# schematic.net
KiCad netlist of a schematic drawn in EAGLE
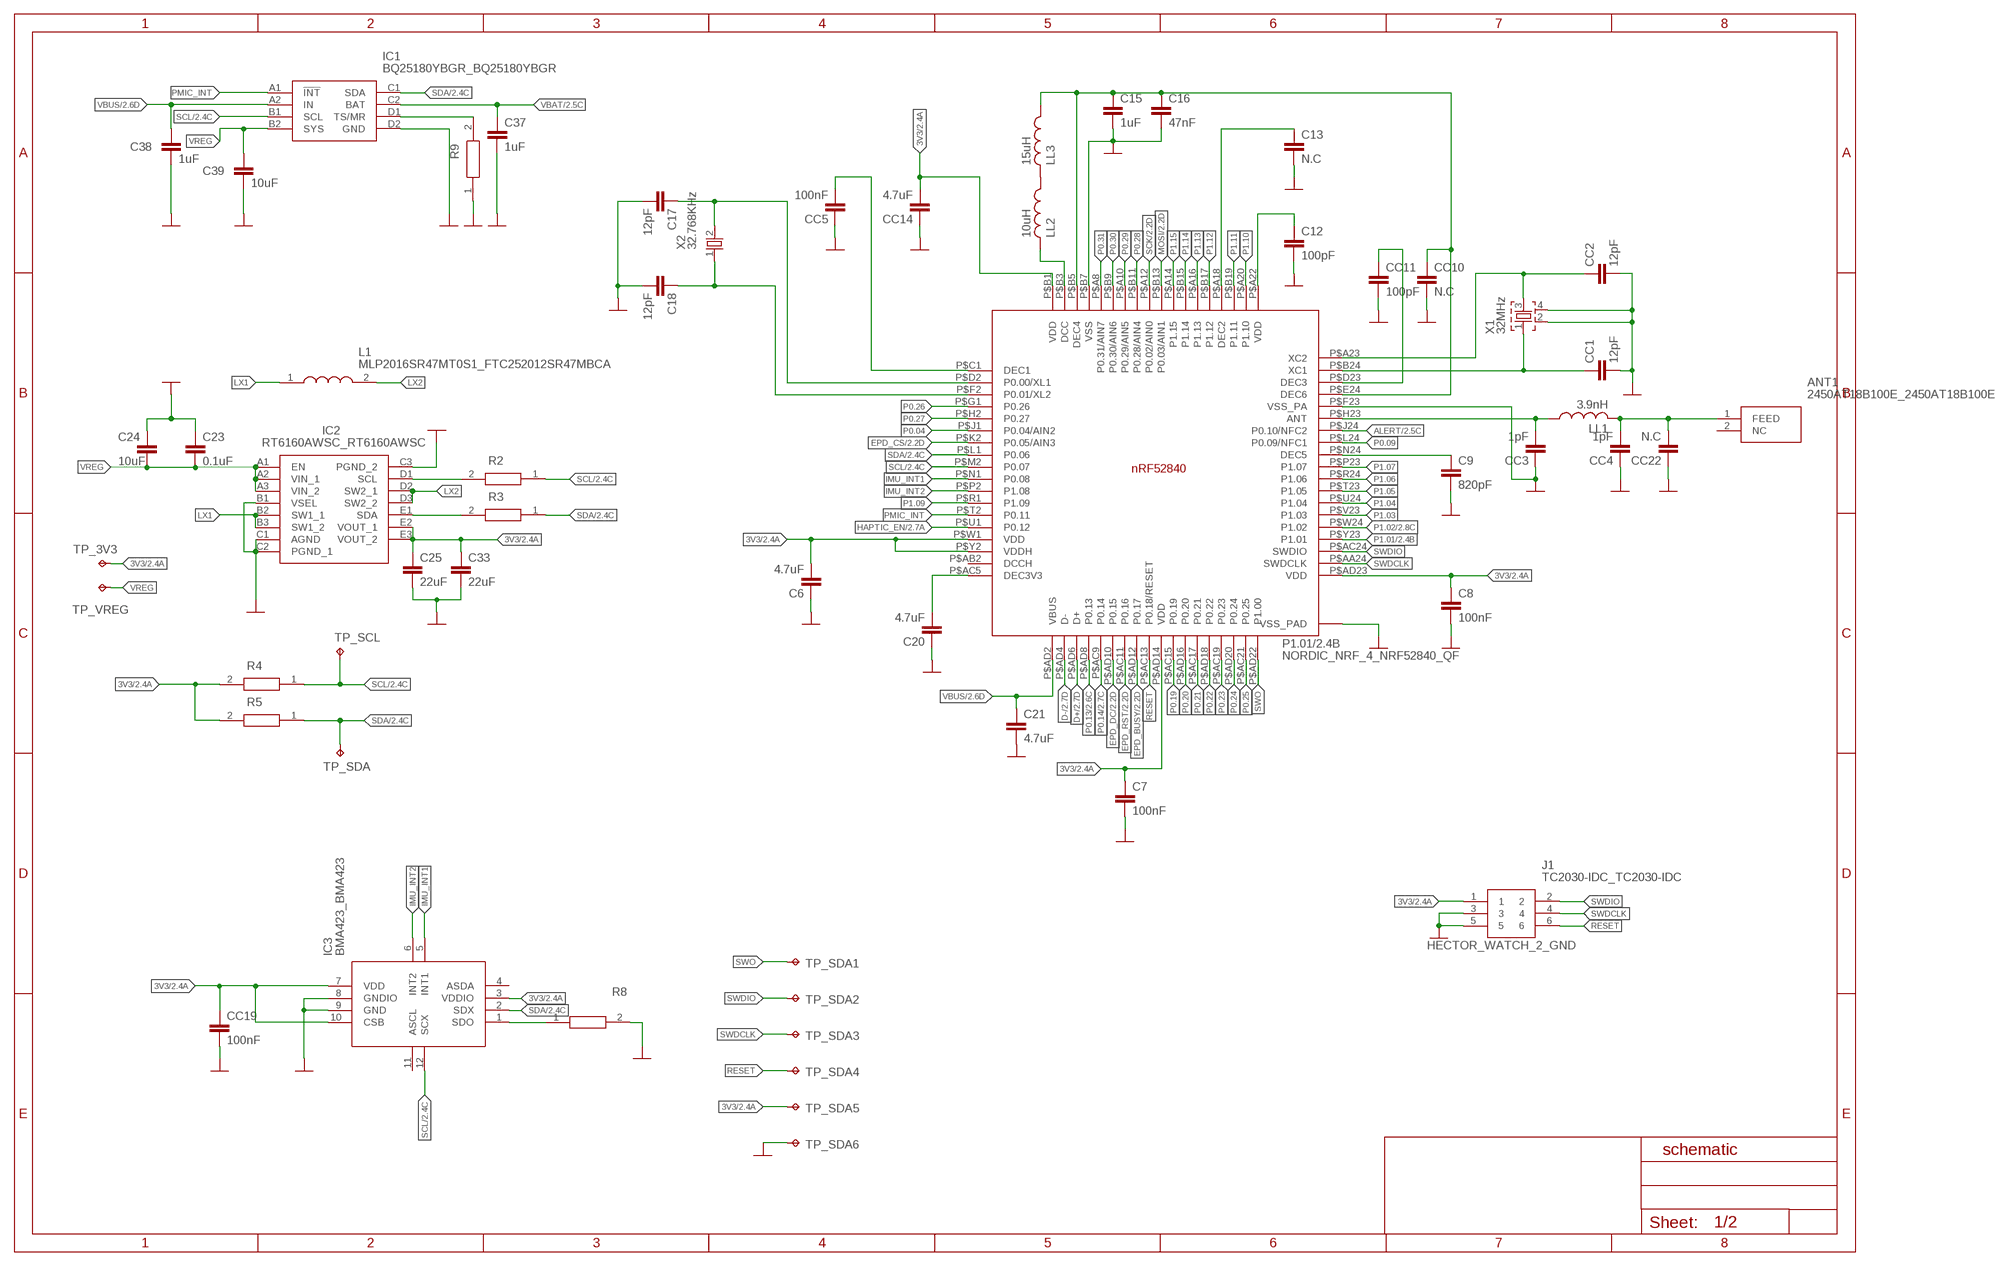
[diagram p0: schematic, sheet 1]
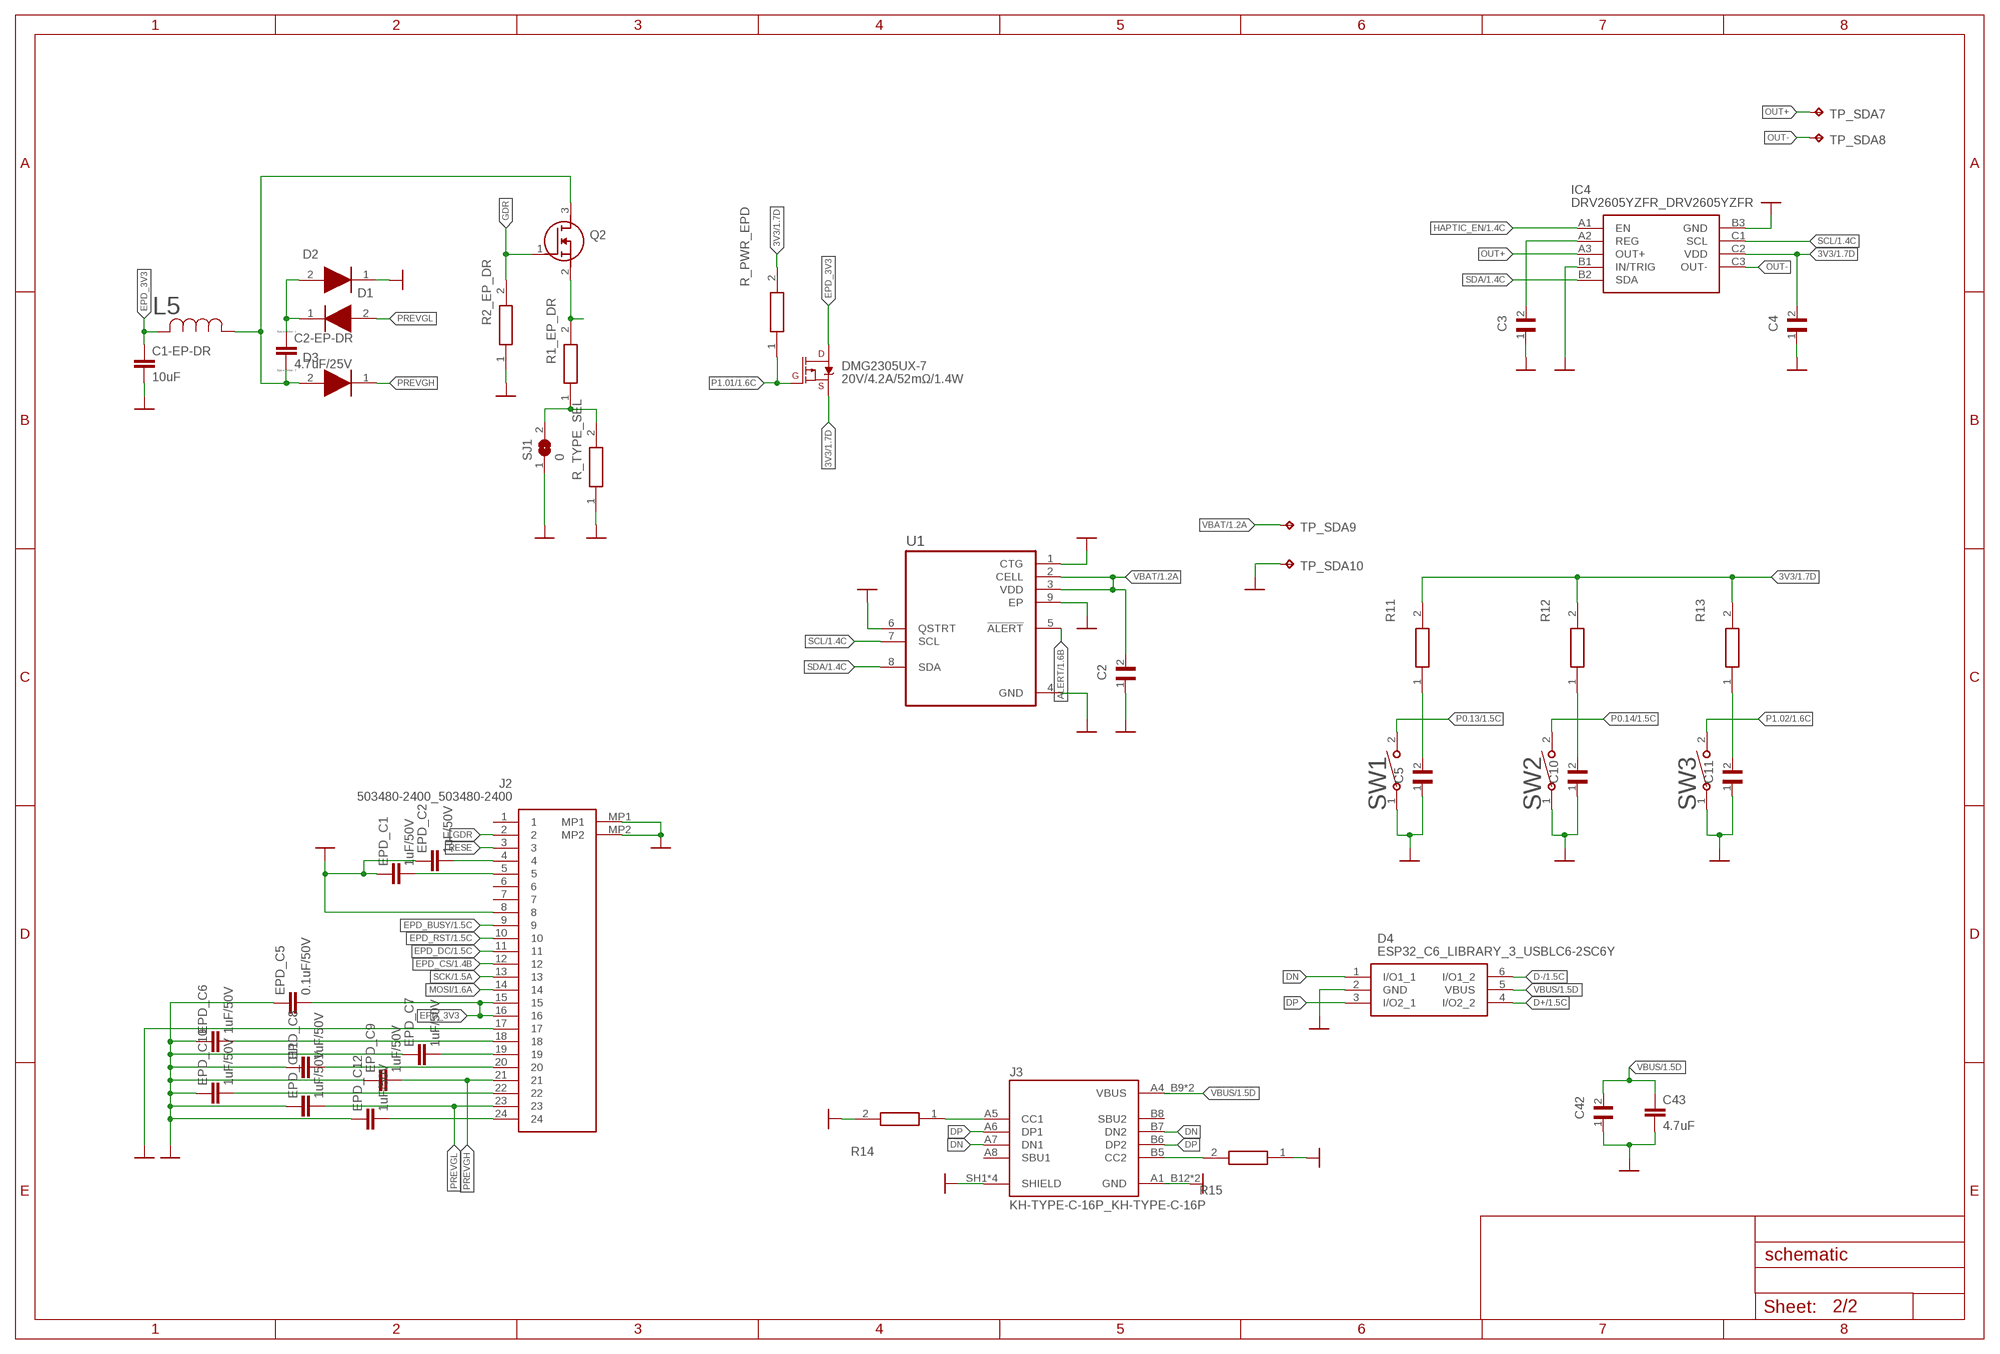
[diagram p1: schematic, sheet 2]

(export (version "E")
  (design (tool "Eeschema 10.0.6"))
  (components
    (comp (ref "ANT1")
      (value "2450AT18B100E_2450AT18B100E")
      (footprint "eagle-import:2450AT18B100E_ANTC3216X140N")
      (fields
        (field (name "ARROW_PART_NUMBER") "2450AT18B100E")
        (field (name "MOUSER_PART_NUMBER") "609-2450AT18B100E")
      )
      (libsource (lib "eagle-import") (part "2450AT18B100E_2450AT18B100E"))
    )
    (comp (ref "C6")
      (value "4.7uF")
      (footprint "eagle-import:NORDIC_NRF_3_RESC0402_M")
      (libsource (lib "eagle-import") (part "NORDIC_NRF_3_CAPACITOR_0402_M"))
    )
    (comp (ref "C7")
      (value "100nF")
      (footprint "eagle-import:NORDIC_NRF_3_RESC0402_M")
      (libsource (lib "eagle-import") (part "NORDIC_NRF_3_CAPACITOR_0402_M"))
    )
    (comp (ref "C8")
      (value "100nF")
      (footprint "eagle-import:NORDIC_NRF_3_RESC0402_M")
      (libsource (lib "eagle-import") (part "NORDIC_NRF_3_CAPACITOR_0402_M"))
    )
    (comp (ref "C9")
      (value "820pF")
      (footprint "eagle-import:NORDIC_NRF_3_RESC0402_M")
      (libsource (lib "eagle-import") (part "NORDIC_NRF_3_CAPACITOR_0402_M"))
    )
    (comp (ref "C12")
      (value "100pF")
      (footprint "eagle-import:NORDIC_NRF_3_RESC0402_M")
      (libsource (lib "eagle-import") (part "NORDIC_NRF_3_CAPACITOR_0402_M"))
    )
    (comp (ref "C13")
      (value "N.C")
      (footprint "eagle-import:NORDIC_NRF_3_RESC0402_M")
      (libsource (lib "eagle-import") (part "NORDIC_NRF_3_CAPACITOR_0402_M"))
    )
    (comp (ref "C15")
      (value "1uF")
      (footprint "eagle-import:NORDIC_NRF_3_RESC0402_M")
      (libsource (lib "eagle-import") (part "NORDIC_NRF_3_CAPACITOR_0402_M"))
    )
    (comp (ref "C16")
      (value "47nF")
      (footprint "eagle-import:NORDIC_NRF_3_RESC0402_M")
      (libsource (lib "eagle-import") (part "NORDIC_NRF_3_CAPACITOR_0402_M"))
    )
    (comp (ref "C17")
      (value "12pF")
      (footprint "eagle-import:NORDIC_NRF_3_RESC0402_M")
      (libsource (lib "eagle-import") (part "NORDIC_NRF_3_CAPACITOR_0402_M"))
    )
    (comp (ref "C18")
      (value "12pF")
      (footprint "eagle-import:NORDIC_NRF_3_RESC0402_M")
      (libsource (lib "eagle-import") (part "NORDIC_NRF_3_CAPACITOR_0402_M"))
    )
    (comp (ref "C20")
      (value "4.7uF")
      (footprint "eagle-import:NORDIC_NRF_3_RESC0402_M")
      (libsource (lib "eagle-import") (part "NORDIC_NRF_3_CAPACITOR_0402_M"))
    )
    (comp (ref "C21")
      (value "4.7uF")
      (footprint "eagle-import:NORDIC_NRF_3_RESC0402_M")
      (libsource (lib "eagle-import") (part "NORDIC_NRF_3_CAPACITOR_0402_M"))
    )
    (comp (ref "C23")
      (value "0.1uF")
      (footprint "eagle-import:NORDIC_NRF_3_RESC0402_M")
      (libsource (lib "eagle-import") (part "NORDIC_NRF_3_CAPACITOR_0402_M"))
    )
    (comp (ref "C24")
      (value "10uF")
      (footprint "eagle-import:NORDIC_NRF_3_RESC0402_M")
      (libsource (lib "eagle-import") (part "NORDIC_NRF_3_CAPACITOR_0402_M"))
    )
    (comp (ref "C25")
      (value "22uF")
      (footprint "eagle-import:NORDIC_NRF_3_RESC0402_M")
      (libsource (lib "eagle-import") (part "NORDIC_NRF_3_CAPACITOR_0402_M"))
    )
    (comp (ref "C33")
      (value "22uF")
      (footprint "eagle-import:NORDIC_NRF_3_RESC0402_M")
      (libsource (lib "eagle-import") (part "NORDIC_NRF_3_CAPACITOR_0402_M"))
    )
    (comp (ref "C37")
      (value "1uF")
      (footprint "eagle-import:NORDIC_NRF_3_RESC0402_M")
      (libsource (lib "eagle-import") (part "NORDIC_NRF_3_CAPACITOR_0402_M"))
    )
    (comp (ref "C38")
      (value "1uF")
      (footprint "eagle-import:NORDIC_NRF_3_RESC0402_M")
      (libsource (lib "eagle-import") (part "NORDIC_NRF_3_CAPACITOR_0402_M"))
    )
    (comp (ref "C39")
      (value "10uF")
      (footprint "eagle-import:NORDIC_NRF_3_RESC0402_M")
      (libsource (lib "eagle-import") (part "NORDIC_NRF_3_CAPACITOR_0402_M"))
    )
    (comp (ref "CC1")
      (value "12pF")
      (footprint "eagle-import:NORDIC_NRF_3_RESC0402_M")
      (libsource (lib "eagle-import") (part "NORDIC_NRF_3_CAPACITOR_0402_M"))
    )
    (comp (ref "CC2")
      (value "12pF")
      (footprint "eagle-import:NORDIC_NRF_3_RESC0402_M")
      (libsource (lib "eagle-import") (part "NORDIC_NRF_3_CAPACITOR_0402_M"))
    )
    (comp (ref "CC3")
      (value "1pF")
      (footprint "eagle-import:NORDIC_NRF_3_RESC0402_M")
      (libsource (lib "eagle-import") (part "NORDIC_NRF_3_CAPACITOR_0402_M"))
    )
    (comp (ref "CC4")
      (value "1pF")
      (footprint "eagle-import:NORDIC_NRF_3_RESC0402_M")
      (libsource (lib "eagle-import") (part "NORDIC_NRF_3_CAPACITOR_0402_M"))
    )
    (comp (ref "CC5")
      (value "100nF")
      (footprint "eagle-import:NORDIC_NRF_3_RESC0402_M")
      (libsource (lib "eagle-import") (part "NORDIC_NRF_3_CAPACITOR_0402_M"))
    )
    (comp (ref "CC10")
      (value "N.C")
      (footprint "eagle-import:NORDIC_NRF_3_RESC0402_M")
      (libsource (lib "eagle-import") (part "NORDIC_NRF_3_CAPACITOR_0402_M"))
    )
    (comp (ref "CC11")
      (value "100pF")
      (footprint "eagle-import:NORDIC_NRF_3_RESC0402_M")
      (libsource (lib "eagle-import") (part "NORDIC_NRF_3_CAPACITOR_0402_M"))
    )
    (comp (ref "CC14")
      (value "4.7uF")
      (footprint "eagle-import:NORDIC_NRF_3_RESC0402_M")
      (libsource (lib "eagle-import") (part "NORDIC_NRF_3_CAPACITOR_0402_M"))
    )
    (comp (ref "CC19")
      (value "100nF")
      (footprint "eagle-import:NORDIC_NRF_3_RESC0402_M")
      (libsource (lib "eagle-import") (part "NORDIC_NRF_3_CAPACITOR_0402_M"))
    )
    (comp (ref "CC22")
      (value "N.C")
      (footprint "eagle-import:NORDIC_NRF_3_RESC0402_M")
      (libsource (lib "eagle-import") (part "NORDIC_NRF_3_CAPACITOR_0402_M"))
    )
    (comp (ref "IC1")
      (value "BQ25180YBGR_BQ25180YBGR")
      (footprint "eagle-import:BQ25180YBGR_BGA8C40P2X4_100X155X50")
      (fields
        (field (name "ARROW_PART_NUMBER") "BQ25180YBGR")
        (field (name "MOUSER_PART_NUMBER") "595-BQ25180YBGR")
      )
      (libsource (lib "eagle-import") (part "BQ25180YBGR_BQ25180YBGR"))
    )
    (comp (ref "IC2")
      (value "RT6160AWSC_RT6160AWSC")
      (footprint "eagle-import:RT6160AWSC_BGA15C40P3X5_140X230X60")
      (fields
        (field (name "MANUFACTURER_PART_NUMBER") "RT6160AWSC")
        (field (name "MOUSER_PART_NUMBER") "835-RT6160AWSC")
      )
      (libsource (lib "eagle-import") (part "RT6160AWSC_RT6160AWSC"))
    )
    (comp (ref "IC3")
      (value "BMA423_BMA423")
      (footprint "eagle-import:BMA423_BMA423")
      (fields (field (name "ARROW_PART_NUMBER") "BMA423") (field (name "MOUSER_PART_NUMBER") "262-BMA423"))
      (libsource (lib "eagle-import") (part "BMA423_BMA423"))
    )
    (comp (ref "J1")
      (value "TC2030-IDC_TC2030-IDC")
      (footprint "eagle-import:TC2030-IDC_TC2030IDC")
      (fields (field (name "MANUFACTURER_PART_NUMBER") "TC2030-IDC"))
      (libsource (lib "eagle-import") (part "TC2030-IDC_TC2030-IDC"))
    )
    (comp (ref "L1")
      (value "MLP2016SR47MT0S1_FTC252012SR47MBCA")
      (footprint "eagle-import:MLP2016SR47MT0S1_INDC2016X100N")
      (fields (field (name "MANUFACTURER_PART_NUMBER") "FTC252012SR47MBCA"))
      (libsource (lib "eagle-import") (part "MLP2016SR47MT0S1_FTC252012SR47MBCA"))
    )
    (comp (ref "LL1")
      (value "3.9nH")
      (footprint "eagle-import:NORDIC_NRF_2_RESC0402_M")
      (libsource (lib "eagle-import") (part "NORDIC_NRF_2_INDUCTOR_0402_M"))
    )
    (comp (ref "LL2")
      (value "10uH")
      (footprint "eagle-import:NORDIC_NRF_2_RESC0402_M")
      (libsource (lib "eagle-import") (part "NORDIC_NRF_2_INDUCTOR_0402_M"))
    )
    (comp (ref "LL3")
      (value "15uH")
      (footprint "eagle-import:NORDIC_NRF_2_RESC0402_M")
      (libsource (lib "eagle-import") (part "NORDIC_NRF_2_INDUCTOR_0402_M"))
    )
    (comp (ref "P1.01/2.4B")
      (value "NORDIC_NRF_4_NRF52840_QF")
      (footprint "eagle-import:NORDIC_NRF_4_AQFN50P700X700X85_HS-74N")
      (libsource (lib "eagle-import") (part "NORDIC_NRF_4_NRF52840_QF"))
    )
    (comp (ref "R2")
      (value "CPF0201D7K68C1_CPF0201D7K68C1")
      (footprint "eagle-import:CPF0201D7K68C1_0201")
      (libsource (lib "eagle-import") (part "CPF0201D7K68C1_CPF0201D7K68C1"))
    )
    (comp (ref "R3")
      (value "CPF0201D7K68C1_CPF0201D7K68C1")
      (footprint "eagle-import:CPF0201D7K68C1_0201")
      (libsource (lib "eagle-import") (part "CPF0201D7K68C1_CPF0201D7K68C1"))
    )
    (comp (ref "R4")
      (value "CPF0201D7K68C1_CPF0201D7K68C1")
      (footprint "eagle-import:CPF0201D7K68C1_0201")
      (libsource (lib "eagle-import") (part "CPF0201D7K68C1_CPF0201D7K68C1"))
    )
    (comp (ref "R5")
      (value "CPF0201D7K68C1_CPF0201D7K68C1")
      (footprint "eagle-import:CPF0201D7K68C1_0201")
      (libsource (lib "eagle-import") (part "CPF0201D7K68C1_CPF0201D7K68C1"))
    )
    (comp (ref "R8")
      (value "CPF0201D7K68C1_CPF0201D7K68C1")
      (footprint "eagle-import:CPF0201D7K68C1_0201")
      (libsource (lib "eagle-import") (part "CPF0201D7K68C1_CPF0201D7K68C1"))
    )
    (comp (ref "R9")
      (value "10K")
      (footprint "eagle-import:CPF0201D7K68C1_0201")
      (libsource (lib "eagle-import") (part "CPF0201D7K68C1_CPF0201D7K68C1"))
    )
    (comp (ref "TP_3V3")
      (value "HECTOR_WATCH_1_TPTP20R")
      (footprint "eagle-import:HECTOR_WATCH_1_TP20R")
      (libsource (lib "eagle-import") (part "HECTOR_WATCH_1_TPTP20R"))
    )
    (comp (ref "TP_SCL")
      (value "HECTOR_WATCH_1_TPTP20R")
      (footprint "eagle-import:HECTOR_WATCH_1_TP20R")
      (libsource (lib "eagle-import") (part "HECTOR_WATCH_1_TPTP20R"))
    )
    (comp (ref "TP_SDA")
      (value "HECTOR_WATCH_1_TPTP20R")
      (footprint "eagle-import:HECTOR_WATCH_1_TP20R")
      (libsource (lib "eagle-import") (part "HECTOR_WATCH_1_TPTP20R"))
    )
    (comp (ref "TP_SDA1")
      (value "HECTOR_WATCH_1_TPTP20R")
      (footprint "eagle-import:HECTOR_WATCH_1_TP20R")
      (libsource (lib "eagle-import") (part "HECTOR_WATCH_1_TPTP20R"))
    )
    (comp (ref "TP_SDA2")
      (value "HECTOR_WATCH_1_TPTP20R")
      (footprint "eagle-import:HECTOR_WATCH_1_TP20R")
      (libsource (lib "eagle-import") (part "HECTOR_WATCH_1_TPTP20R"))
    )
    (comp (ref "TP_SDA3")
      (value "HECTOR_WATCH_1_TPTP20R")
      (footprint "eagle-import:HECTOR_WATCH_1_TP20R")
      (libsource (lib "eagle-import") (part "HECTOR_WATCH_1_TPTP20R"))
    )
    (comp (ref "TP_SDA4")
      (value "HECTOR_WATCH_1_TPTP20R")
      (footprint "eagle-import:HECTOR_WATCH_1_TP20R")
      (libsource (lib "eagle-import") (part "HECTOR_WATCH_1_TPTP20R"))
    )
    (comp (ref "TP_SDA5")
      (value "HECTOR_WATCH_1_TPTP20R")
      (footprint "eagle-import:HECTOR_WATCH_1_TP20R")
      (libsource (lib "eagle-import") (part "HECTOR_WATCH_1_TPTP20R"))
    )
    (comp (ref "TP_SDA6")
      (value "HECTOR_WATCH_1_TPTP20R")
      (footprint "eagle-import:HECTOR_WATCH_1_TP20R")
      (libsource (lib "eagle-import") (part "HECTOR_WATCH_1_TPTP20R"))
    )
    (comp (ref "TP_VREG")
      (value "HECTOR_WATCH_1_TPTP20R")
      (footprint "eagle-import:HECTOR_WATCH_1_TP20R")
      (libsource (lib "eagle-import") (part "HECTOR_WATCH_1_TPTP20R"))
    )
    (comp (ref "X1")
      (value "32MHz")
      (footprint "eagle-import:NORDIC_NRF_BT-XTAL_2016_N")
      (libsource (lib "eagle-import") (part "NORDIC_NRF_XTAL_32MHZ"))
    )
    (comp (ref "X2")
      (value "32.768KHz")
      (footprint "eagle-import:NORDIC_NRF_1_XTAL_3215_N")
      (libsource (lib "eagle-import") (part "NORDIC_NRF_1_XTAL_32KHZ"))
    )
    (comp (ref "C1-EP-DR")
      (value "10uF")
      (footprint "eagle-import:NORDIC_NRF_3_RESC0402_M")
      (libsource (lib "eagle-import") (part "NORDIC_NRF_3_CAPACITOR_0402_M"))
    )
    (comp (ref "C2")
      (value "GRM011R60J152KE01L_1_GRM011R60J152KE01L")
      (footprint "eagle-import:GRM011R60J152KE01L_1_0201")
      (libsource (lib "eagle-import") (part "GRM011R60J152KE01L_1_GRM011R60J152KE01L"))
    )
    (comp (ref "C2-EP-DR")
      (value "4.7uF/25V")
      (footprint "eagle-import:ESP32_C6_LIBRARY_1_ESP32_WROVER_EAGLE-LTSPICE_C0402")
      (libsource (lib "eagle-import") (part "ESP32_C6_LIBRARY_1_ESP32_WROVER_EAGLE-LTSPICE_CC0402"))
    )
    (comp (ref "C3")
      (value "1uF")
      (footprint "eagle-import:GRM011R60J152KE01L_1_0201")
      (libsource (lib "eagle-import") (part "GRM011R60J152KE01L_1_GRM011R60J152KE01L"))
    )
    (comp (ref "C4")
      (value "0.1uF")
      (footprint "eagle-import:GRM011R60J152KE01L_1_0201")
      (libsource (lib "eagle-import") (part "GRM011R60J152KE01L_1_GRM011R60J152KE01L"))
    )
    (comp (ref "C5")
      (value "GRM011R60J152KE01L_1_GRM011R60J152KE01L")
      (footprint "eagle-import:GRM011R60J152KE01L_1_0201")
      (libsource (lib "eagle-import") (part "GRM011R60J152KE01L_1_GRM011R60J152KE01L"))
    )
    (comp (ref "C10")
      (value "GRM011R60J152KE01L_1_GRM011R60J152KE01L")
      (footprint "eagle-import:GRM011R60J152KE01L_1_0201")
      (libsource (lib "eagle-import") (part "GRM011R60J152KE01L_1_GRM011R60J152KE01L"))
    )
    (comp (ref "C11")
      (value "GRM011R60J152KE01L_1_GRM011R60J152KE01L")
      (footprint "eagle-import:GRM011R60J152KE01L_1_0201")
      (libsource (lib "eagle-import") (part "GRM011R60J152KE01L_1_GRM011R60J152KE01L"))
    )
    (comp (ref "C42")
      (value "GRM011R60J152KE01L_1_GRM011R60J152KE01L")
      (footprint "eagle-import:GRM011R60J152KE01L_1_0201")
      (libsource (lib "eagle-import") (part "GRM011R60J152KE01L_1_GRM011R60J152KE01L"))
    )
    (comp (ref "C43")
      (value "4.7uF")
      (footprint "eagle-import:NORDIC_NRF_3_RESC0402_M")
      (libsource (lib "eagle-import") (part "NORDIC_NRF_3_CAPACITOR_0402_M"))
    )
    (comp (ref "D1")
      (value "ESP32_C6_LIBRARY_5_MBR0530")
      (footprint "eagle-import:ESP32_C6_LIBRARY_5_SOD3716X135N")
      (fields (field (name "MF") "ON Semiconductor") (field (name "MP") "MBR0530"))
      (libsource (lib "eagle-import") (part "ESP32_C6_LIBRARY_5_MBR0530"))
    )
    (comp (ref "D2")
      (value "ESP32_C6_LIBRARY_5_MBR0530")
      (footprint "eagle-import:ESP32_C6_LIBRARY_5_SOD3716X135N")
      (fields (field (name "MF") "ON Semiconductor") (field (name "MP") "MBR0530"))
      (libsource (lib "eagle-import") (part "ESP32_C6_LIBRARY_5_MBR0530"))
    )
    (comp (ref "D3")
      (value "ESP32_C6_LIBRARY_5_MBR0530")
      (footprint "eagle-import:ESP32_C6_LIBRARY_5_SOD3716X135N")
      (fields (field (name "MF") "ON Semiconductor") (field (name "MP") "MBR0530"))
      (libsource (lib "eagle-import") (part "ESP32_C6_LIBRARY_5_MBR0530"))
    )
    (comp (ref "D4")
      (value "ESP32_C6_LIBRARY_3_USBLC6-2SC6Y")
      (footprint "eagle-import:ESP32_C6_LIBRARY_3_SOT95P280X145-6N")
      (fields (field (name "MF") "STMicroelectronics") (field (name "MP") "USBLC6-2SC6Y"))
      (libsource (lib "eagle-import") (part "ESP32_C6_LIBRARY_3_USBLC6-2SC6Y"))
    )
    (comp (ref "DMG2305UX-7")
      (value "20V/4.2A/52mΩ/1.4W")
      (footprint "eagle-import:ESP32_C6_LIBRARY_4_ESP32_C6_LIBRARY_4_ESP32_C6_LIBRARY_4_ESP32_C6_LIBRARY_4_ESP32_WROVER_SPARKFUN-DISCRETESEMI_SOT23-3")
      (libsource (lib "eagle-import") (part "ESP32_C6_LIBRARY_4_ESP32_WROVER_SPARKFUN-DISCRETESEMI_MOSFET_PCH-DMG2305UX-7"))
    )
    (comp (ref "EPD_C1")
      (value "1uF/50V")
      (footprint "eagle-import:NORDIC_NRF_3_RESC0402_M")
      (libsource (lib "eagle-import") (part "NORDIC_NRF_3_CAPACITOR_0402_M"))
    )
    (comp (ref "EPD_C2")
      (value "1uF/50V")
      (footprint "eagle-import:NORDIC_NRF_3_RESC0402_M")
      (libsource (lib "eagle-import") (part "NORDIC_NRF_3_CAPACITOR_0402_M"))
    )
    (comp (ref "EPD_C5")
      (value "0.1uF/50V")
      (footprint "eagle-import:NORDIC_NRF_3_RESC0402_M")
      (libsource (lib "eagle-import") (part "NORDIC_NRF_3_CAPACITOR_0402_M"))
    )
    (comp (ref "EPD_C6")
      (value "1uF/50V")
      (footprint "eagle-import:NORDIC_NRF_3_RESC0402_M")
      (libsource (lib "eagle-import") (part "NORDIC_NRF_3_CAPACITOR_0402_M"))
    )
    (comp (ref "EPD_C7")
      (value "1uF/50V")
      (footprint "eagle-import:NORDIC_NRF_3_RESC0402_M")
      (libsource (lib "eagle-import") (part "NORDIC_NRF_3_CAPACITOR_0402_M"))
    )
    (comp (ref "EPD_C8")
      (value "1uF/50V")
      (footprint "eagle-import:NORDIC_NRF_3_RESC0402_M")
      (libsource (lib "eagle-import") (part "NORDIC_NRF_3_CAPACITOR_0402_M"))
    )
    (comp (ref "EPD_C9")
      (value "1uF/50V")
      (footprint "eagle-import:NORDIC_NRF_3_RESC0402_M")
      (libsource (lib "eagle-import") (part "NORDIC_NRF_3_CAPACITOR_0402_M"))
    )
    (comp (ref "EPD_C10")
      (value "1uF/50V")
      (footprint "eagle-import:NORDIC_NRF_3_RESC0402_M")
      (libsource (lib "eagle-import") (part "NORDIC_NRF_3_CAPACITOR_0402_M"))
    )
    (comp (ref "EPD_C11")
      (value "1uF/50V")
      (footprint "eagle-import:NORDIC_NRF_3_RESC0402_M")
      (libsource (lib "eagle-import") (part "NORDIC_NRF_3_CAPACITOR_0402_M"))
    )
    (comp (ref "EPD_C12")
      (value "1uF/50V")
      (footprint "eagle-import:NORDIC_NRF_3_RESC0402_M")
      (libsource (lib "eagle-import") (part "NORDIC_NRF_3_CAPACITOR_0402_M"))
    )
    (comp (ref "IC4")
      (value "DRV2605YZFR_DRV2605YZFR")
      (footprint "eagle-import:DRV2605YZFR_BGA9C50P3X3_144X144X62")
      (fields (field (name "ARROW_PART_NUMBER") "DRV2605YZFR"))
      (libsource (lib "eagle-import") (part "DRV2605YZFR_DRV2605YZFR"))
    )
    (comp (ref "J2")
      (value "503480-2400_503480-2400")
      (footprint "eagle-import:503480-2400_5034802400")
      (fields
        (field (name "MANUFACTURER_PART_NUMBER") "503480-2400")
        (field (name "MOUSER_PART_NUMBER") "538-503480-2400")
      )
      (libsource (lib "eagle-import") (part "503480-2400_503480-2400"))
    )
    (comp (ref "J3")
      (value "KH-TYPE-C-16P_KH-TYPE-C-16P")
      (footprint "eagle-import:KH-TYPE-C-16P_KINGHELM_KH-TYPE-C-16P")
      (fields (field (name "MF") "kinghelm") (field (name "MP") "KH-TYPE-C-16P"))
      (libsource (lib "eagle-import") (part "KH-TYPE-C-16P_KH-TYPE-C-16P"))
    )
    (comp (ref "L5")
      (value "ESP32_C6_LIBRARY_2_744043680IND_4828-WE-TPC_WRE")
      (footprint "eagle-import:ESP32_C6_LIBRARY_2_IND_4828-WE-TPC_WRE")
      (fields
        (field (name "MANUFACTURER_PART_NUMBER") "744043680")
        (field (name "COPYRIGHT") "Copyright (C) 2024 Ultra Librarian. All rights reserved.")
      )
      (libsource (lib "eagle-import") (part "ESP32_C6_LIBRARY_2_744043680IND_4828-WE-TPC_WRE"))
    )
    (comp (ref "Q2")
      (value "ESP32_C6_LIBRARY_6_SI1308EDL-T1-GE3")
      (footprint "eagle-import:ESP32_C6_LIBRARY_6_SOT65P210X110-3N")
      (fields (field (name "MF") "Vishay Siliconix") (field (name "MP") "SI1308EDL-T1-GE3"))
      (libsource (lib "eagle-import") (part "ESP32_C6_LIBRARY_6_SI1308EDL-T1-GE3"))
    )
    (comp (ref "R1_EP_DR")
      (value "CPF0201D7K68C1_CPF0201D7K68C1")
      (footprint "eagle-import:CPF0201D7K68C1_0201")
      (libsource (lib "eagle-import") (part "CPF0201D7K68C1_CPF0201D7K68C1"))
    )
    (comp (ref "R2_EP_DR")
      (value "CPF0201D7K68C1_CPF0201D7K68C1")
      (footprint "eagle-import:CPF0201D7K68C1_0201")
      (libsource (lib "eagle-import") (part "CPF0201D7K68C1_CPF0201D7K68C1"))
    )
    (comp (ref "R11")
      (value "CPF0201D7K68C1_CPF0201D7K68C1")
      (footprint "eagle-import:CPF0201D7K68C1_0201")
      (libsource (lib "eagle-import") (part "CPF0201D7K68C1_CPF0201D7K68C1"))
    )
    (comp (ref "R12")
      (value "CPF0201D7K68C1_CPF0201D7K68C1")
      (footprint "eagle-import:CPF0201D7K68C1_0201")
      (libsource (lib "eagle-import") (part "CPF0201D7K68C1_CPF0201D7K68C1"))
    )
    (comp (ref "R13")
      (value "CPF0201D7K68C1_CPF0201D7K68C1")
      (footprint "eagle-import:CPF0201D7K68C1_0201")
      (libsource (lib "eagle-import") (part "CPF0201D7K68C1_CPF0201D7K68C1"))
    )
    (comp (ref "R14")
      (value "CPF0201D7K68C1_CPF0201D7K68C1")
      (footprint "eagle-import:CPF0201D7K68C1_0201")
      (libsource (lib "eagle-import") (part "CPF0201D7K68C1_CPF0201D7K68C1"))
    )
    (comp (ref "R15")
      (value "CPF0201D7K68C1_CPF0201D7K68C1")
      (footprint "eagle-import:CPF0201D7K68C1_0201")
      (libsource (lib "eagle-import") (part "CPF0201D7K68C1_CPF0201D7K68C1"))
    )
    (comp (ref "R_PWR_EPD")
      (value "CPF0201D7K68C1_CPF0201D7K68C1")
      (footprint "eagle-import:CPF0201D7K68C1_0201")
      (libsource (lib "eagle-import") (part "CPF0201D7K68C1_CPF0201D7K68C1"))
    )
    (comp (ref "R_TYPE_SEL")
      (value "CPF0201D7K68C1_CPF0201D7K68C1")
      (footprint "eagle-import:CPF0201D7K68C1_0201")
      (libsource (lib "eagle-import") (part "CPF0201D7K68C1_CPF0201D7K68C1"))
    )
    (comp (ref "SJ1")
      (value "0")
      (footprint "eagle-import:ESP32_C6_LIBRARY_7_JUMPER_SJ")
      (libsource (lib "eagle-import") (part "ESP32_C6_LIBRARY_7_JUMPER_SJ"))
    )
    (comp (ref "SW1")
      (value "2025-10-22_07-23-44_LIBRARY_EVP-AKE31ASW_EVP-AKE31A_PAN")
      (footprint "eagle-import:2025-10-22_07-23-44_LIBRARY_SW_EVP-AKE31A_PAN")
      (fields
        (field (name "MANUFACTURER_PART_NUMBER") "EVP-AKE31A")
        (field (name "COPYRIGHT") "Copyright (C) 2025 Ultra Librarian. All rights reserved.")
      )
      (libsource (lib "eagle-import") (part "2025-10-22_07-23-44_LIBRARY_EVP-AKE31ASW_EVP-AKE31A_PAN"))
    )
    (comp (ref "SW2")
      (value "2025-10-22_07-23-44_LIBRARY_EVP-AKE31ASW_EVP-AKE31A_PAN")
      (footprint "eagle-import:2025-10-22_07-23-44_LIBRARY_SW_EVP-AKE31A_PAN")
      (fields
        (field (name "MANUFACTURER_PART_NUMBER") "EVP-AKE31A")
        (field (name "COPYRIGHT") "Copyright (C) 2025 Ultra Librarian. All rights reserved.")
      )
      (libsource (lib "eagle-import") (part "2025-10-22_07-23-44_LIBRARY_EVP-AKE31ASW_EVP-AKE31A_PAN"))
    )
    (comp (ref "SW3")
      (value "2025-10-22_07-23-44_LIBRARY_EVP-AKE31ASW_EVP-AKE31A_PAN")
      (footprint "eagle-import:2025-10-22_07-23-44_LIBRARY_SW_EVP-AKE31A_PAN")
      (fields
        (field (name "MANUFACTURER_PART_NUMBER") "EVP-AKE31A")
        (field (name "COPYRIGHT") "Copyright (C) 2025 Ultra Librarian. All rights reserved.")
      )
      (libsource (lib "eagle-import") (part "2025-10-22_07-23-44_LIBRARY_EVP-AKE31ASW_EVP-AKE31A_PAN"))
    )
    (comp (ref "TP_SDA7")
      (value "HECTOR_WATCH_1_TPTP20R")
      (footprint "eagle-import:HECTOR_WATCH_1_TP20R")
      (libsource (lib "eagle-import") (part "HECTOR_WATCH_1_TPTP20R"))
    )
    (comp (ref "TP_SDA8")
      (value "HECTOR_WATCH_1_TPTP20R")
      (footprint "eagle-import:HECTOR_WATCH_1_TP20R")
      (libsource (lib "eagle-import") (part "HECTOR_WATCH_1_TPTP20R"))
    )
    (comp (ref "TP_SDA9")
      (value "HECTOR_WATCH_1_TPTP20R")
      (footprint "eagle-import:HECTOR_WATCH_1_TP20R")
      (libsource (lib "eagle-import") (part "HECTOR_WATCH_1_TPTP20R"))
    )
    (comp (ref "TP_SDA10")
      (value "HECTOR_WATCH_1_TPTP20R")
      (footprint "eagle-import:HECTOR_WATCH_1_TP20R")
      (libsource (lib "eagle-import") (part "HECTOR_WATCH_1_TPTP20R"))
    )
    (comp (ref "U1")
      (value "ESP32_C6_LIBRARY_MAX17048G+T10")
      (footprint "eagle-import:ESP32_C6_LIBRARY_SON50P200X200X80-9N")
      (fields (field (name "MF") "Analog Devices") (field (name "MP") "MAX17048G+T10"))
      (libsource (lib "eagle-import") (part "ESP32_C6_LIBRARY_MAX17048G+T10"))
    )
  )
  (nets
    (net (code "1") (name "3V3{slash}1.7D") (class "Default")
      (node (ref "C4") (pin "2") (pinfunction "2_2") (pintype "passive"))
      (node (ref "DMG2305UX-7") (pin "2") (pinfunction "S_2") (pintype "bidirectional"))
      (node (ref "IC4") (pin "C2") (pinfunction "VDD_C2") (pintype "bidirectional"))
      (node (ref "R11") (pin "2") (pinfunction "2_2") (pintype "bidirectional"))
      (node (ref "R12") (pin "2") (pinfunction "2_2") (pintype "bidirectional"))
      (node (ref "R13") (pin "2") (pinfunction "2_2") (pintype "bidirectional"))
      (node (ref "R_PWR_EPD") (pin "2") (pinfunction "2_2") (pintype "bidirectional"))
    )
    (net (code "2") (name "3V3{slash}2.4A") (class "Default")
      (node (ref "C25") (pin "1") (pinfunction "1_1") (pintype "passive"))
      (node (ref "C33") (pin "1") (pinfunction "1_1") (pintype "passive"))
      (node (ref "C6") (pin "2") (pinfunction "2_2") (pintype "passive"))
      (node (ref "C7") (pin "1") (pinfunction "1_1") (pintype "passive"))
      (node (ref "C8") (pin "1") (pinfunction "1_1") (pintype "passive"))
      (node (ref "CC14") (pin "2") (pinfunction "2_2") (pintype "passive"))
      (node (ref "CC19") (pin "1") (pinfunction "1_1") (pintype "passive"))
      (node (ref "IC2") (pin "E2") (pinfunction "VOUT_1_E2") (pintype "bidirectional"))
      (node (ref "IC2") (pin "E3") (pinfunction "VOUT_2_E3") (pintype "bidirectional"))
      (node (ref "IC3") (pin "10") (pinfunction "CSB_10") (pintype "bidirectional"))
      (node (ref "IC3") (pin "3") (pinfunction "VDDIO_3") (pintype "bidirectional"))
      (node (ref "IC3") (pin "7") (pinfunction "VDD_7") (pintype "bidirectional"))
      (node (ref "J1") (pin "1") (pinfunction "1_1") (pintype "bidirectional"))
      (node (ref "P1.01/2.4B") (pin "P$AD14") (pinfunction "VDD_P$AD14") (pintype "power_in"))
      (node (ref "P1.01/2.4B") (pin "P$AD23") (pinfunction "VDD_P$AD23") (pintype "power_in"))
      (node (ref "P1.01/2.4B") (pin "P$B1") (pinfunction "VDD_P$B1") (pintype "power_in"))
      (node (ref "P1.01/2.4B") (pin "P$W1") (pinfunction "VDD_P$W1") (pintype "power_in"))
      (node (ref "P1.01/2.4B") (pin "P$Y2") (pinfunction "VDDH_P$Y2") (pintype "power_in"))
      (node (ref "R4") (pin "2") (pinfunction "2_2") (pintype "bidirectional"))
      (node (ref "R5") (pin "2") (pinfunction "2_2") (pintype "bidirectional"))
      (node (ref "TP_3V3") (pin "TP") (pinfunction "TP_TP") (pintype "input"))
      (node (ref "TP_SDA5") (pin "TP") (pinfunction "TP_TP") (pintype "input"))
    )
    (net (code "3") (name "ALERT") (class "Default")
      (node (ref "P1.01/2.4B") (pin "P$J24") (pinfunction "P0.10/NFC2_P$J24") (pintype "bidirectional"))
      (node (ref "U1") (pin "5") (pinfunction "~{ALERT}_5") (pintype "output"))
    )
    (net (code "4") (name "D+") (class "Default")
      (node (ref "D4") (pin "4") (pinfunction "I/O2_2_4") (pintype "bidirectional"))
      (node (ref "P1.01/2.4B") (pin "P$AD6") (pinfunction "D+_P$AD6") (pintype "bidirectional"))
    )
    (net (code "5") (name "D-") (class "Default")
      (node (ref "D4") (pin "6") (pinfunction "I/O1_2_6") (pintype "bidirectional"))
      (node (ref "P1.01/2.4B") (pin "P$AD4") (pinfunction "D-_P$AD4") (pintype "bidirectional"))
    )
    (net (code "6") (name "DN") (class "Default")
      (node (ref "D4") (pin "1") (pinfunction "I/O1_1_1") (pintype "bidirectional"))
      (node (ref "J3") (pin "A7") (pinfunction "DN1_A7") (pintype "bidirectional"))
      (node (ref "J3") (pin "B7") (pinfunction "DN2_B7") (pintype "bidirectional"))
    )
    (net (code "7") (name "DP") (class "Default")
      (node (ref "D4") (pin "3") (pinfunction "I/O2_1_3") (pintype "bidirectional"))
      (node (ref "J3") (pin "A6") (pinfunction "DP1_A6") (pintype "bidirectional"))
      (node (ref "J3") (pin "B6") (pinfunction "DP2_B6") (pintype "bidirectional"))
    )
    (net (code "8") (name "EPD_3V3") (class "Default")
      (node (ref "C1-EP-DR") (pin "1") (pinfunction "1_1") (pintype "passive"))
      (node (ref "DMG2305UX-7") (pin "3") (pinfunction "D_3") (pintype "bidirectional"))
      (node (ref "EPD_C5") (pin "2") (pinfunction "2_2") (pintype "passive"))
      (node (ref "J2") (pin "15") (pinfunction "15_15") (pintype "bidirectional"))
      (node (ref "J2") (pin "16") (pinfunction "16_16") (pintype "bidirectional"))
      (node (ref "L5") (pin "2") (pinfunction "2_2") (pintype "passive"))
    )
    (net (code "9") (name "EPD_BUSY") (class "Default")
      (node (ref "J2") (pin "9") (pinfunction "9_9") (pintype "bidirectional"))
      (node (ref "P1.01/2.4B") (pin "P$AD12") (pinfunction "P0.17_P$AD12") (pintype "bidirectional"))
    )
    (net (code "10") (name "EPD_CS") (class "Default")
      (node (ref "J2") (pin "12") (pinfunction "12_12") (pintype "bidirectional"))
      (node (ref "P1.01/2.4B") (pin "P$K2") (pinfunction "P0.05/AIN3_P$K2") (pintype "bidirectional"))
    )
    (net (code "11") (name "EPD_DC") (class "Default")
      (node (ref "J2") (pin "11") (pinfunction "11_11") (pintype "bidirectional"))
      (node (ref "P1.01/2.4B") (pin "P$AD10") (pinfunction "P0.15_P$AD10") (pintype "bidirectional"))
    )
    (net (code "12") (name "EPD_RST") (class "Default")
      (node (ref "J2") (pin "10") (pinfunction "10_10") (pintype "bidirectional"))
      (node (ref "P1.01/2.4B") (pin "P$AC11") (pinfunction "P0.16_P$AC11") (pintype "bidirectional"))
    )
    (net (code "13") (name "GDR") (class "Default")
      (node (ref "J2") (pin "2") (pinfunction "2_2") (pintype "bidirectional"))
      (node (ref "Q2") (pin "1") (pinfunction "G_1") (pintype "bidirectional"))
      (node (ref "R2_EP_DR") (pin "2") (pinfunction "2_2") (pintype "bidirectional"))
    )
    (net (code "14") (name "GND") (class "Default")
      (node (ref "C1-EP-DR") (pin "2") (pinfunction "2_2") (pintype "passive"))
      (node (ref "C10") (pin "1") (pinfunction "1_1") (pintype "passive"))
      (node (ref "C11") (pin "1") (pinfunction "1_1") (pintype "passive"))
      (node (ref "C12") (pin "2") (pinfunction "2_2") (pintype "passive"))
      (node (ref "C13") (pin "2") (pinfunction "2_2") (pintype "passive"))
      (node (ref "C15") (pin "2") (pinfunction "2_2") (pintype "passive"))
      (node (ref "C16") (pin "2") (pinfunction "2_2") (pintype "passive"))
      (node (ref "C17") (pin "2") (pinfunction "2_2") (pintype "passive"))
      (node (ref "C18") (pin "2") (pinfunction "2_2") (pintype "passive"))
      (node (ref "C2") (pin "1") (pinfunction "1_1") (pintype "passive"))
      (node (ref "C20") (pin "1") (pinfunction "1_1") (pintype "passive"))
      (node (ref "C21") (pin "2") (pinfunction "2_2") (pintype "passive"))
      (node (ref "C23") (pin "1") (pinfunction "1_1") (pintype "passive"))
      (node (ref "C24") (pin "1") (pinfunction "1_1") (pintype "passive"))
      (node (ref "C25") (pin "2") (pinfunction "2_2") (pintype "passive"))
      (node (ref "C3") (pin "1") (pinfunction "1_1") (pintype "passive"))
      (node (ref "C33") (pin "2") (pinfunction "2_2") (pintype "passive"))
      (node (ref "C37") (pin "2") (pinfunction "2_2") (pintype "passive"))
      (node (ref "C38") (pin "2") (pinfunction "2_2") (pintype "passive"))
      (node (ref "C39") (pin "2") (pinfunction "2_2") (pintype "passive"))
      (node (ref "C4") (pin "1") (pinfunction "1_1") (pintype "passive"))
      (node (ref "C42") (pin "1") (pinfunction "1_1") (pintype "passive"))
      (node (ref "C43") (pin "2") (pinfunction "2_2") (pintype "passive"))
      (node (ref "C5") (pin "1") (pinfunction "1_1") (pintype "passive"))
      (node (ref "C6") (pin "1") (pinfunction "1_1") (pintype "passive"))
      (node (ref "C7") (pin "2") (pinfunction "2_2") (pintype "passive"))
      (node (ref "C8") (pin "2") (pinfunction "2_2") (pintype "passive"))
      (node (ref "C9") (pin "2") (pinfunction "2_2") (pintype "passive"))
      (node (ref "CC1") (pin "2") (pinfunction "2_2") (pintype "passive"))
      (node (ref "CC10") (pin "2") (pinfunction "2_2") (pintype "passive"))
      (node (ref "CC11") (pin "2") (pinfunction "2_2") (pintype "passive"))
      (node (ref "CC14") (pin "1") (pinfunction "1_1") (pintype "passive"))
      (node (ref "CC19") (pin "2") (pinfunction "2_2") (pintype "passive"))
      (node (ref "CC2") (pin "2") (pinfunction "2_2") (pintype "passive"))
      (node (ref "CC22") (pin "1") (pinfunction "1_1") (pintype "passive"))
      (node (ref "CC3") (pin "1") (pinfunction "1_1") (pintype "passive"))
      (node (ref "CC4") (pin "1") (pinfunction "1_1") (pintype "passive"))
      (node (ref "CC5") (pin "1") (pinfunction "1_1") (pintype "passive"))
      (node (ref "D2") (pin "1") (pinfunction "K_1") (pintype "bidirectional"))
      (node (ref "D4") (pin "2") (pinfunction "GND_2") (pintype "bidirectional"))
      (node (ref "EPD_C1") (pin "1") (pinfunction "1_1") (pintype "passive"))
      (node (ref "EPD_C10") (pin "1") (pinfunction "1_1") (pintype "passive"))
      (node (ref "EPD_C11") (pin "1") (pinfunction "1_1") (pintype "passive"))
      (node (ref "EPD_C12") (pin "1") (pinfunction "1_1") (pintype "passive"))
      (node (ref "EPD_C2") (pin "1") (pinfunction "1_1") (pintype "passive"))
      (node (ref "EPD_C5") (pin "1") (pinfunction "1_1") (pintype "passive"))
      (node (ref "EPD_C6") (pin "1") (pinfunction "1_1") (pintype "passive"))
      (node (ref "EPD_C7") (pin "1") (pinfunction "1_1") (pintype "passive"))
      (node (ref "EPD_C8") (pin "1") (pinfunction "1_1") (pintype "passive"))
      (node (ref "EPD_C9") (pin "1") (pinfunction "1_1") (pintype "passive"))
      (node (ref "IC1") (pin "D2") (pinfunction "GND_D2") (pintype "bidirectional"))
      (node (ref "IC2") (pin "B1") (pinfunction "VSEL_B1") (pintype "bidirectional"))
      (node (ref "IC2") (pin "C1") (pinfunction "AGND_C1") (pintype "bidirectional"))
      (node (ref "IC2") (pin "C2") (pinfunction "PGND_1_C2") (pintype "bidirectional"))
      (node (ref "IC2") (pin "C3") (pinfunction "PGND_2_C3") (pintype "bidirectional"))
      (node (ref "IC3") (pin "8") (pinfunction "GNDIO_8") (pintype "bidirectional"))
      (node (ref "IC3") (pin "9") (pinfunction "GND_9") (pintype "bidirectional"))
      (node (ref "IC4") (pin "B1") (pinfunction "IN/TRIG_B1") (pintype "bidirectional"))
      (node (ref "IC4") (pin "B3") (pinfunction "GND_B3") (pintype "bidirectional"))
      (node (ref "J1") (pin "3") (pinfunction "3_3") (pintype "bidirectional"))
      (node (ref "J1") (pin "5") (pinfunction "5_5") (pintype "bidirectional"))
      (node (ref "J2") (pin "17") (pinfunction "17_17") (pintype "bidirectional"))
      (node (ref "J2") (pin "8") (pinfunction "8_8") (pintype "bidirectional"))
      (node (ref "J2") (pin "MP1") (pinfunction "MP1_MP1") (pintype "bidirectional"))
      (node (ref "J2") (pin "MP2") (pinfunction "MP2_MP2") (pintype "bidirectional"))
      (node (ref "J3") (pin "A12_B1") (pinfunction "GND_A12_B1") (pintype "power_in"))
      (node (ref "J3") (pin "A1_B12") (pinfunction "GND_A1_B12") (pintype "power_in"))
      (node (ref "J3") (pin "SH1") (pinfunction "SHIELD_SH1") (pintype "passive"))
      (node (ref "J3") (pin "SH2") (pinfunction "SHIELD_SH2") (pintype "passive"))
      (node (ref "J3") (pin "SH3") (pinfunction "SHIELD_SH3") (pintype "passive"))
      (node (ref "J3") (pin "SH4") (pinfunction "SHIELD_SH4") (pintype "passive"))
      (node (ref "P1.01/2.4B") (pin "P$74") (pinfunction "VSS_PAD_P$74") (pintype "bidirectional"))
      (node (ref "P1.01/2.4B") (pin "P$75") (pinfunction "VSS_PAD_P$75") (pintype "bidirectional"))
      (node (ref "P1.01/2.4B") (pin "P$76") (pinfunction "VSS_PAD_P$76") (pintype "bidirectional"))
      (node (ref "P1.01/2.4B") (pin "P$77") (pinfunction "VSS_PAD_P$77") (pintype "bidirectional"))
      (node (ref "P1.01/2.4B") (pin "P$78") (pinfunction "VSS_PAD_P$78") (pintype "bidirectional"))
      (node (ref "P1.01/2.4B") (pin "P$79") (pinfunction "VSS_PAD_P$79") (pintype "bidirectional"))
      (node (ref "P1.01/2.4B") (pin "P$80") (pinfunction "VSS_PAD_P$80") (pintype "bidirectional"))
      (node (ref "P1.01/2.4B") (pin "P$81") (pinfunction "VSS_PAD_P$81") (pintype "bidirectional"))
      (node (ref "P1.01/2.4B") (pin "P$82") (pinfunction "VSS_PAD_P$82") (pintype "bidirectional"))
      (node (ref "P1.01/2.4B") (pin "P$83") (pinfunction "VSS_PAD_P$83") (pintype "bidirectional"))
      (node (ref "P1.01/2.4B") (pin "P$84") (pinfunction "VSS_PAD_P$84") (pintype "bidirectional"))
      (node (ref "P1.01/2.4B") (pin "P$85") (pinfunction "VSS_PAD_P$85") (pintype "bidirectional"))
      (node (ref "P1.01/2.4B") (pin "P$86") (pinfunction "VSS_PAD_P$86") (pintype "bidirectional"))
      (node (ref "P1.01/2.4B") (pin "P$87") (pinfunction "VSS_PAD_P$87") (pintype "bidirectional"))
      (node (ref "P1.01/2.4B") (pin "P$88") (pinfunction "VSS_PAD_P$88") (pintype "bidirectional"))
      (node (ref "P1.01/2.4B") (pin "P$89") (pinfunction "VSS_PAD_P$89") (pintype "bidirectional"))
      (node (ref "P1.01/2.4B") (pin "P$90") (pinfunction "VSS_PAD_P$90") (pintype "bidirectional"))
      (node (ref "P1.01/2.4B") (pin "P$B7") (pinfunction "VSS_P$B7") (pintype "power_in"))
      (node (ref "P1.01/2.4B") (pin "P$F23") (pinfunction "VSS_PA_P$F23") (pintype "bidirectional"))
      (node (ref "R14") (pin "2") (pinfunction "2_2") (pintype "bidirectional"))
      (node (ref "R15") (pin "1") (pinfunction "1_1") (pintype "bidirectional"))
      (node (ref "R2_EP_DR") (pin "1") (pinfunction "1_1") (pintype "bidirectional"))
      (node (ref "R8") (pin "2") (pinfunction "2_2") (pintype "bidirectional"))
      (node (ref "R9") (pin "1") (pinfunction "1_1") (pintype "bidirectional"))
      (node (ref "R_TYPE_SEL") (pin "1") (pinfunction "1_1") (pintype "bidirectional"))
      (node (ref "SJ1") (pin "1") (pinfunction "1_1") (pintype "passive"))
      (node (ref "SW1") (pin "1") (pinfunction "1_1") (pintype "passive"))
      (node (ref "SW2") (pin "1") (pinfunction "1_1") (pintype "passive"))
      (node (ref "SW3") (pin "1") (pinfunction "1_1") (pintype "passive"))
      (node (ref "TP_SDA10") (pin "TP") (pinfunction "TP_TP") (pintype "input"))
      (node (ref "TP_SDA6") (pin "TP") (pinfunction "TP_TP") (pintype "input"))
      (node (ref "U1") (pin "1") (pinfunction "CTG_1") (pintype "power_in"))
      (node (ref "U1") (pin "4") (pinfunction "GND_4") (pintype "power_in"))
      (node (ref "U1") (pin "6") (pinfunction "QSTRT_6") (pintype "input"))
      (node (ref "U1") (pin "9") (pinfunction "EP_9") (pintype "power_in"))
      (node (ref "X1") (pin "2") (pinfunction "2_2") (pintype "passive"))
      (node (ref "X1") (pin "4") (pinfunction "4_4") (pintype "passive"))
    )
    (net (code "15") (name "HAPTIC_EN") (class "Default")
      (node (ref "IC4") (pin "A1") (pinfunction "EN_A1") (pintype "bidirectional"))
      (node (ref "P1.01/2.4B") (pin "P$U1") (pinfunction "P0.12_P$U1") (pintype "bidirectional"))
    )
    (net (code "16") (name "IMU_INT1") (class "Default")
      (node (ref "IC3") (pin "5") (pinfunction "INT1_5") (pintype "bidirectional"))
      (node (ref "P1.01/2.4B") (pin "P$N1") (pinfunction "P0.08_P$N1") (pintype "bidirectional"))
    )
    (net (code "17") (name "IMU_INT2") (class "Default")
      (node (ref "IC3") (pin "6") (pinfunction "INT2_6") (pintype "bidirectional"))
      (node (ref "P1.01/2.4B") (pin "P$P2") (pinfunction "P1.08_P$P2") (pintype "bidirectional"))
    )
    (net (code "18") (name "LX1") (class "Default")
      (node (ref "IC2") (pin "B2") (pinfunction "SW1_1_B2") (pintype "bidirectional"))
      (node (ref "IC2") (pin "B3") (pinfunction "SW1_2_B3") (pintype "bidirectional"))
      (node (ref "L1") (pin "1") (pinfunction "1_1") (pintype "bidirectional"))
    )
    (net (code "19") (name "LX2") (class "Default")
      (node (ref "IC2") (pin "D2") (pinfunction "SW2_1_D2") (pintype "bidirectional"))
      (node (ref "IC2") (pin "D3") (pinfunction "SW2_2_D3") (pintype "bidirectional"))
      (node (ref "L1") (pin "2") (pinfunction "2_2") (pintype "bidirectional"))
    )
    (net (code "20") (name "MOSI") (class "Default")
      (node (ref "J2") (pin "14") (pinfunction "14_14") (pintype "bidirectional"))
      (node (ref "P1.01/2.4B") (pin "P$B13") (pinfunction "P0.03/AIN1_P$B13") (pintype "bidirectional"))
    )
    (net (code "21") (name "Net-(ANT1-FEED)") (class "Default")
      (node (ref "ANT1") (pin "1") (pinfunction "FEED_1") (pintype "input"))
      (node (ref "CC22") (pin "2") (pinfunction "2_2") (pintype "passive"))
      (node (ref "CC4") (pin "2") (pinfunction "2_2") (pintype "passive"))
      (node (ref "LL1") (pin "2") (pinfunction "2_2") (pintype "passive"))
    )
    (net (code "22") (name "Net-(C5-Pad2)") (class "Default")
      (node (ref "C5") (pin "2") (pinfunction "2_2") (pintype "passive"))
      (node (ref "R11") (pin "1") (pinfunction "1_1") (pintype "bidirectional"))
    )
    (net (code "23") (name "Net-(C10-Pad2)") (class "Default")
      (node (ref "C10") (pin "2") (pinfunction "2_2") (pintype "passive"))
      (node (ref "R12") (pin "1") (pinfunction "1_1") (pintype "bidirectional"))
    )
    (net (code "24") (name "Net-(C11-Pad2)") (class "Default")
      (node (ref "C11") (pin "2") (pinfunction "2_2") (pintype "passive"))
      (node (ref "R13") (pin "1") (pinfunction "1_1") (pintype "bidirectional"))
    )
    (net (code "25") (name "Net-(C12-Pad1)") (class "Default")
      (node (ref "C12") (pin "1") (pinfunction "1_1") (pintype "passive"))
      (node (ref "P1.01/2.4B") (pin "P$A22") (pinfunction "VDD_P$A22") (pintype "power_in"))
    )
    (net (code "26") (name "Net-(D1-K)") (class "Default")
      (node (ref "C2-EP-DR") (pin "1") (pinfunction "1_1") (pintype "passive"))
      (node (ref "D1") (pin "1") (pinfunction "K_1") (pintype "bidirectional"))
      (node (ref "D2") (pin "2") (pinfunction "A_2") (pintype "bidirectional"))
    )
    (net (code "27") (name "Net-(D3-A)") (class "Default")
      (node (ref "C2-EP-DR") (pin "2") (pinfunction "2_2") (pintype "passive"))
      (node (ref "D3") (pin "2") (pinfunction "A_2") (pintype "bidirectional"))
      (node (ref "L5") (pin "1") (pinfunction "1_1") (pintype "passive"))
      (node (ref "Q2") (pin "3") (pinfunction "D_3") (pintype "bidirectional"))
    )
    (net (code "28") (name "Net-(EPD_C1-Pad2)") (class "Default")
      (node (ref "EPD_C1") (pin "2") (pinfunction "2_2") (pintype "passive"))
      (node (ref "J2") (pin "5") (pinfunction "5_5") (pintype "bidirectional"))
    )
    (net (code "29") (name "Net-(EPD_C2-Pad2)") (class "Default")
      (node (ref "EPD_C2") (pin "2") (pinfunction "2_2") (pintype "passive"))
      (node (ref "J2") (pin "4") (pinfunction "4_4") (pintype "bidirectional"))
    )
    (net (code "30") (name "Net-(EPD_C6-Pad2)") (class "Default")
      (node (ref "EPD_C6") (pin "2") (pinfunction "2_2") (pintype "passive"))
      (node (ref "J2") (pin "18") (pinfunction "18_18") (pintype "bidirectional"))
    )
    (net (code "31") (name "Net-(EPD_C7-Pad2)") (class "Default")
      (node (ref "EPD_C7") (pin "2") (pinfunction "2_2") (pintype "passive"))
      (node (ref "J2") (pin "19") (pinfunction "19_19") (pintype "bidirectional"))
    )
    (net (code "32") (name "Net-(EPD_C8-Pad2)") (class "Default")
      (node (ref "EPD_C8") (pin "2") (pinfunction "2_2") (pintype "passive"))
      (node (ref "J2") (pin "20") (pinfunction "20_20") (pintype "bidirectional"))
    )
    (net (code "33") (name "Net-(EPD_C10-Pad2)") (class "Default")
      (node (ref "EPD_C10") (pin "2") (pinfunction "2_2") (pintype "passive"))
      (node (ref "J2") (pin "22") (pinfunction "22_22") (pintype "bidirectional"))
    )
    (net (code "34") (name "Net-(EPD_C12-Pad2)") (class "Default")
      (node (ref "EPD_C12") (pin "2") (pinfunction "2_2") (pintype "passive"))
      (node (ref "J2") (pin "24") (pinfunction "24_24") (pintype "bidirectional"))
    )
    (net (code "35") (name "Net-(IC1-TS{slash}MR)") (class "Default")
      (node (ref "IC1") (pin "D1") (pinfunction "TS/MR_D1") (pintype "bidirectional"))
      (node (ref "R9") (pin "2") (pinfunction "2_2") (pintype "bidirectional"))
    )
    (net (code "36") (name "Net-(IC2-SCL)") (class "Default")
      (node (ref "IC2") (pin "D1") (pinfunction "SCL_D1") (pintype "bidirectional"))
      (node (ref "R2") (pin "2") (pinfunction "2_2") (pintype "bidirectional"))
    )
    (net (code "37") (name "Net-(IC2-SDA)") (class "Default")
      (node (ref "IC2") (pin "E1") (pinfunction "SDA_E1") (pintype "bidirectional"))
      (node (ref "R3") (pin "2") (pinfunction "2_2") (pintype "bidirectional"))
    )
    (net (code "38") (name "Net-(IC3-SDO)") (class "Default")
      (node (ref "IC3") (pin "1") (pinfunction "SDO_1") (pintype "bidirectional"))
      (node (ref "R8") (pin "1") (pinfunction "1_1") (pintype "bidirectional"))
    )
    (net (code "39") (name "Net-(IC4-REG)") (class "Default")
      (node (ref "C3") (pin "2") (pinfunction "2_2") (pintype "passive"))
      (node (ref "IC4") (pin "A2") (pinfunction "REG_A2") (pintype "bidirectional"))
    )
    (net (code "40") (name "Net-(J3-CC1)") (class "Default")
      (node (ref "J3") (pin "A5") (pinfunction "CC1_A5") (pintype "bidirectional"))
      (node (ref "R14") (pin "1") (pinfunction "1_1") (pintype "bidirectional"))
    )
    (net (code "41") (name "Net-(J3-CC2)") (class "Default")
      (node (ref "J3") (pin "B5") (pinfunction "CC2_B5") (pintype "bidirectional"))
      (node (ref "R15") (pin "2") (pinfunction "2_2") (pintype "bidirectional"))
    )
    (net (code "42") (name "Net-(LL2-Pad1)") (class "Default")
      (node (ref "LL2") (pin "1") (pinfunction "1_1") (pintype "passive"))
      (node (ref "LL3") (pin "2") (pinfunction "2_2") (pintype "passive"))
    )
    (net (code "43") (name "Net-(P1.01/2.4B-ANT)") (class "Default")
      (node (ref "CC3") (pin "2") (pinfunction "2_2") (pintype "passive"))
      (node (ref "LL1") (pin "1") (pinfunction "1_1") (pintype "passive"))
      (node (ref "P1.01/2.4B") (pin "P$H23") (pinfunction "ANT_P$H23") (pintype "bidirectional"))
    )
    (net (code "44") (name "Net-(P1.01/2.4B-DCC)") (class "Default")
      (node (ref "LL2") (pin "2") (pinfunction "2_2") (pintype "passive"))
      (node (ref "P1.01/2.4B") (pin "P$B3") (pinfunction "DCC_P$B3") (pintype "output"))
    )
    (net (code "45") (name "Net-(P1.01/2.4B-DEC1)") (class "Default")
      (node (ref "CC5") (pin "2") (pinfunction "2_2") (pintype "passive"))
      (node (ref "P1.01/2.4B") (pin "P$C1") (pinfunction "DEC1_P$C1") (pintype "power_in"))
    )
    (net (code "46") (name "Net-(P1.01/2.4B-DEC2)") (class "Default")
      (node (ref "C13") (pin "1") (pinfunction "1_1") (pintype "passive"))
      (node (ref "P1.01/2.4B") (pin "P$A18") (pinfunction "DEC2_P$A18") (pintype "bidirectional"))
    )
    (net (code "47") (name "Net-(P1.01/2.4B-DEC3)") (class "Default")
      (node (ref "CC11") (pin "1") (pinfunction "1_1") (pintype "passive"))
      (node (ref "P1.01/2.4B") (pin "P$D23") (pinfunction "DEC3_P$D23") (pintype "bidirectional"))
    )
    (net (code "48") (name "Net-(P1.01/2.4B-DEC3V3)") (class "Default")
      (node (ref "C20") (pin "2") (pinfunction "2_2") (pintype "passive"))
      (node (ref "P1.01/2.4B") (pin "P$AC5") (pinfunction "DEC3V3_P$AC5") (pintype "bidirectional"))
    )
    (net (code "49") (name "Net-(P1.01/2.4B-DEC4)") (class "Default")
      (node (ref "C15") (pin "1") (pinfunction "1_1") (pintype "passive"))
      (node (ref "C16") (pin "1") (pinfunction "1_1") (pintype "passive"))
      (node (ref "CC10") (pin "1") (pinfunction "1_1") (pintype "passive"))
      (node (ref "LL3") (pin "1") (pinfunction "1_1") (pintype "passive"))
      (node (ref "P1.01/2.4B") (pin "P$B5") (pinfunction "DEC4_P$B5") (pintype "power_in"))
      (node (ref "P1.01/2.4B") (pin "P$E24") (pinfunction "DEC6_P$E24") (pintype "bidirectional"))
    )
    (net (code "50") (name "Net-(P1.01/2.4B-DEC5)") (class "Default")
      (node (ref "C9") (pin "1") (pinfunction "1_1") (pintype "passive"))
      (node (ref "P1.01/2.4B") (pin "P$N24") (pinfunction "DEC5_P$N24") (pintype "bidirectional"))
    )
    (net (code "51") (name "Net-(P1.01/2.4B-P0.00{slash}XL1)") (class "Default")
      (node (ref "C17") (pin "1") (pinfunction "1_1") (pintype "passive"))
      (node (ref "P1.01/2.4B") (pin "P$D2") (pinfunction "P0.00/XL1_P$D2") (pintype "bidirectional"))
      (node (ref "X2") (pin "2") (pinfunction "2_2") (pintype "passive"))
    )
    (net (code "52") (name "Net-(P1.01/2.4B-P0.01{slash}XL2)") (class "Default")
      (node (ref "C18") (pin "1") (pinfunction "1_1") (pintype "passive"))
      (node (ref "P1.01/2.4B") (pin "P$F2") (pinfunction "P0.01/XL2_P$F2") (pintype "bidirectional"))
      (node (ref "X2") (pin "1") (pinfunction "1_1") (pintype "passive"))
    )
    (net (code "53") (name "Net-(P1.01/2.4B-XC1)") (class "Default")
      (node (ref "CC1") (pin "1") (pinfunction "1_1") (pintype "passive"))
      (node (ref "P1.01/2.4B") (pin "P$B24") (pinfunction "XC1_P$B24") (pintype "input"))
      (node (ref "X1") (pin "1") (pinfunction "1_1") (pintype "passive"))
    )
    (net (code "54") (name "Net-(P1.01/2.4B-XC2)") (class "Default")
      (node (ref "CC2") (pin "1") (pinfunction "1_1") (pintype "passive"))
      (node (ref "P1.01/2.4B") (pin "P$A23") (pinfunction "XC2_P$A23") (pintype "output"))
      (node (ref "X1") (pin "3") (pinfunction "3_3") (pintype "passive"))
    )
    (net (code "55") (name "Net-(Q2-S)") (class "Default")
      (node (ref "Q2") (pin "2") (pinfunction "S_2") (pintype "bidirectional"))
      (node (ref "R1_EP_DR") (pin "2") (pinfunction "2_2") (pintype "bidirectional"))
    )
    (net (code "56") (name "Net-(R1_EP_DR-Pad1)") (class "Default")
      (node (ref "R1_EP_DR") (pin "1") (pinfunction "1_1") (pintype "bidirectional"))
      (node (ref "R_TYPE_SEL") (pin "2") (pinfunction "2_2") (pintype "bidirectional"))
      (node (ref "SJ1") (pin "2") (pinfunction "2_2") (pintype "passive"))
    )
    (net (code "57") (name "OUT+") (class "Default")
      (node (ref "IC4") (pin "A3") (pinfunction "OUT+_A3") (pintype "bidirectional"))
      (node (ref "TP_SDA7") (pin "TP") (pinfunction "TP_TP") (pintype "input"))
    )
    (net (code "58") (name "OUT-") (class "Default")
      (node (ref "IC4") (pin "C3") (pinfunction "OUT-_C3") (pintype "bidirectional"))
      (node (ref "TP_SDA8") (pin "TP") (pinfunction "TP_TP") (pintype "input"))
    )
    (net (code "59") (name "P0.04") (class "Default")
      (node (ref "P1.01/2.4B") (pin "P$J1") (pinfunction "P0.04/AIN2_P$J1") (pintype "bidirectional"))
    )
    (net (code "60") (name "P0.09") (class "Default")
      (node (ref "P1.01/2.4B") (pin "P$L24") (pinfunction "P0.09/NFC1_P$L24") (pintype "bidirectional"))
    )
    (net (code "61") (name "P0.13") (class "Default")
      (node (ref "P1.01/2.4B") (pin "P$AD8") (pinfunction "P0.13_P$AD8") (pintype "bidirectional"))
      (node (ref "SW1") (pin "2") (pinfunction "2_2") (pintype "passive"))
    )
    (net (code "62") (name "P0.14") (class "Default")
      (node (ref "P1.01/2.4B") (pin "P$AC9") (pinfunction "P0.14_P$AC9") (pintype "bidirectional"))
      (node (ref "SW2") (pin "2") (pinfunction "2_2") (pintype "passive"))
    )
    (net (code "63") (name "P0.19") (class "Default")
      (node (ref "P1.01/2.4B") (pin "P$AC15") (pinfunction "P0.19_P$AC15") (pintype "bidirectional"))
    )
    (net (code "64") (name "P0.20") (class "Default")
      (node (ref "P1.01/2.4B") (pin "P$AD16") (pinfunction "P0.20_P$AD16") (pintype "bidirectional"))
    )
    (net (code "65") (name "P0.21") (class "Default")
      (node (ref "P1.01/2.4B") (pin "P$AC17") (pinfunction "P0.21_P$AC17") (pintype "bidirectional"))
    )
    (net (code "66") (name "P0.22") (class "Default")
      (node (ref "P1.01/2.4B") (pin "P$AD18") (pinfunction "P0.22_P$AD18") (pintype "bidirectional"))
    )
    (net (code "67") (name "P0.23") (class "Default")
      (node (ref "P1.01/2.4B") (pin "P$AC19") (pinfunction "P0.23_P$AC19") (pintype "bidirectional"))
    )
    (net (code "68") (name "P0.24") (class "Default")
      (node (ref "P1.01/2.4B") (pin "P$AD20") (pinfunction "P0.24_P$AD20") (pintype "bidirectional"))
    )
    (net (code "69") (name "P0.25") (class "Default")
      (node (ref "P1.01/2.4B") (pin "P$AC21") (pinfunction "P0.25_P$AC21") (pintype "bidirectional"))
    )
    (net (code "70") (name "P0.26") (class "Default")
      (node (ref "P1.01/2.4B") (pin "P$G1") (pinfunction "P0.26_P$G1") (pintype "bidirectional"))
    )
    (net (code "71") (name "P0.27") (class "Default")
      (node (ref "P1.01/2.4B") (pin "P$H2") (pinfunction "P0.27_P$H2") (pintype "bidirectional"))
    )
    (net (code "72") (name "P0.28") (class "Default")
      (node (ref "P1.01/2.4B") (pin "P$B11") (pinfunction "P0.28/AIN4_P$B11") (pintype "bidirectional"))
    )
    (net (code "73") (name "P0.29") (class "Default")
      (node (ref "P1.01/2.4B") (pin "P$A10") (pinfunction "P0.29/AIN5_P$A10") (pintype "bidirectional"))
    )
    (net (code "74") (name "P0.30") (class "Default")
      (node (ref "P1.01/2.4B") (pin "P$B9") (pinfunction "P0.30/AIN6_P$B9") (pintype "bidirectional"))
    )
    (net (code "75") (name "P0.31") (class "Default")
      (node (ref "P1.01/2.4B") (pin "P$A8") (pinfunction "P0.31/AIN7_P$A8") (pintype "bidirectional"))
    )
    (net (code "76") (name "P1.01") (class "Default")
      (node (ref "DMG2305UX-7") (pin "1") (pinfunction "G_1") (pintype "bidirectional"))
      (node (ref "P1.01/2.4B") (pin "P$Y23") (pinfunction "P1.01_P$Y23") (pintype "bidirectional"))
      (node (ref "R_PWR_EPD") (pin "1") (pinfunction "1_1") (pintype "bidirectional"))
    )
    (net (code "77") (name "P1.02") (class "Default")
      (node (ref "P1.01/2.4B") (pin "P$W24") (pinfunction "P1.02_P$W24") (pintype "bidirectional"))
      (node (ref "SW3") (pin "2") (pinfunction "2_2") (pintype "passive"))
    )
    (net (code "78") (name "P1.03") (class "Default")
      (node (ref "P1.01/2.4B") (pin "P$V23") (pinfunction "P1.03_P$V23") (pintype "bidirectional"))
    )
    (net (code "79") (name "P1.04") (class "Default")
      (node (ref "P1.01/2.4B") (pin "P$U24") (pinfunction "P1.04_P$U24") (pintype "bidirectional"))
    )
    (net (code "80") (name "P1.05") (class "Default")
      (node (ref "P1.01/2.4B") (pin "P$T23") (pinfunction "P1.05_P$T23") (pintype "bidirectional"))
    )
    (net (code "81") (name "P1.06") (class "Default")
      (node (ref "P1.01/2.4B") (pin "P$R24") (pinfunction "P1.06_P$R24") (pintype "bidirectional"))
    )
    (net (code "82") (name "P1.07") (class "Default")
      (node (ref "P1.01/2.4B") (pin "P$P23") (pinfunction "P1.07_P$P23") (pintype "bidirectional"))
    )
    (net (code "83") (name "P1.09") (class "Default")
      (node (ref "P1.01/2.4B") (pin "P$R1") (pinfunction "P1.09_P$R1") (pintype "bidirectional"))
    )
    (net (code "84") (name "P1.10") (class "Default")
      (node (ref "P1.01/2.4B") (pin "P$A20") (pinfunction "P1.10_P$A20") (pintype "bidirectional"))
    )
    (net (code "85") (name "P1.11") (class "Default")
      (node (ref "P1.01/2.4B") (pin "P$B19") (pinfunction "P1.11_P$B19") (pintype "bidirectional"))
    )
    (net (code "86") (name "P1.12") (class "Default")
      (node (ref "P1.01/2.4B") (pin "P$B17") (pinfunction "P1.12_P$B17") (pintype "bidirectional"))
    )
    (net (code "87") (name "P1.13") (class "Default")
      (node (ref "P1.01/2.4B") (pin "P$A16") (pinfunction "P1.13_P$A16") (pintype "bidirectional"))
    )
    (net (code "88") (name "P1.14") (class "Default")
      (node (ref "P1.01/2.4B") (pin "P$B15") (pinfunction "P1.14_P$B15") (pintype "bidirectional"))
    )
    (net (code "89") (name "P1.15") (class "Default")
      (node (ref "P1.01/2.4B") (pin "P$A14") (pinfunction "P1.15_P$A14") (pintype "bidirectional"))
    )
    (net (code "90") (name "PMIC_INT") (class "Default")
      (node (ref "IC1") (pin "A1") (pinfunction "~{INT}_A1") (pintype "bidirectional"))
      (node (ref "P1.01/2.4B") (pin "P$T2") (pinfunction "P0.11_P$T2") (pintype "bidirectional"))
    )
    (net (code "91") (name "PREVGH") (class "Default")
      (node (ref "D3") (pin "1") (pinfunction "K_1") (pintype "bidirectional"))
      (node (ref "EPD_C9") (pin "2") (pinfunction "2_2") (pintype "passive"))
      (node (ref "J2") (pin "21") (pinfunction "21_21") (pintype "bidirectional"))
    )
    (net (code "92") (name "PREVGL") (class "Default")
      (node (ref "D1") (pin "2") (pinfunction "A_2") (pintype "bidirectional"))
      (node (ref "EPD_C11") (pin "2") (pinfunction "2_2") (pintype "passive"))
      (node (ref "J2") (pin "23") (pinfunction "23_23") (pintype "bidirectional"))
    )
    (net (code "93") (name "RESE") (class "Default")
      (node (ref "J2") (pin "3") (pinfunction "3_3") (pintype "bidirectional"))
    )
    (net (code "94") (name "RESET") (class "Default")
      (node (ref "J1") (pin "6") (pinfunction "6_6") (pintype "bidirectional"))
      (node (ref "P1.01/2.4B") (pin "P$AC13") (pinfunction "P0.18/RESET_P$AC13") (pintype "bidirectional"))
      (node (ref "TP_SDA4") (pin "TP") (pinfunction "TP_TP") (pintype "input"))
    )
    (net (code "95") (name "SCK") (class "Default")
      (node (ref "J2") (pin "13") (pinfunction "13_13") (pintype "bidirectional"))
      (node (ref "P1.01/2.4B") (pin "P$A12") (pinfunction "P0.02/AIN0_P$A12") (pintype "bidirectional"))
    )
    (net (code "96") (name "SCL{slash}1.4C") (class "Default")
      (node (ref "IC4") (pin "C1") (pinfunction "SCL_C1") (pintype "bidirectional"))
      (node (ref "U1") (pin "7") (pinfunction "SCL_7") (pintype "input"))
    )
    (net (code "97") (name "SCL{slash}2.4C") (class "Default")
      (node (ref "IC1") (pin "B1") (pinfunction "SCL_B1") (pintype "bidirectional"))
      (node (ref "IC3") (pin "12") (pinfunction "SCX_12") (pintype "bidirectional"))
      (node (ref "P1.01/2.4B") (pin "P$M2") (pinfunction "P0.07_P$M2") (pintype "bidirectional"))
      (node (ref "R2") (pin "1") (pinfunction "1_1") (pintype "bidirectional"))
      (node (ref "R4") (pin "1") (pinfunction "1_1") (pintype "bidirectional"))
      (node (ref "TP_SCL") (pin "TP") (pinfunction "TP_TP") (pintype "input"))
    )
    (net (code "98") (name "SDA{slash}1.4C") (class "Default")
      (node (ref "IC4") (pin "B2") (pinfunction "SDA_B2") (pintype "bidirectional"))
      (node (ref "U1") (pin "8") (pinfunction "SDA_8") (pintype "bidirectional"))
    )
    (net (code "99") (name "SDA{slash}2.4C") (class "Default")
      (node (ref "IC1") (pin "C1") (pinfunction "SDA_C1") (pintype "bidirectional"))
      (node (ref "IC3") (pin "2") (pinfunction "SDX_2") (pintype "bidirectional"))
      (node (ref "P1.01/2.4B") (pin "P$L1") (pinfunction "P0.06_P$L1") (pintype "bidirectional"))
      (node (ref "R3") (pin "1") (pinfunction "1_1") (pintype "bidirectional"))
      (node (ref "R5") (pin "1") (pinfunction "1_1") (pintype "bidirectional"))
      (node (ref "TP_SDA") (pin "TP") (pinfunction "TP_TP") (pintype "input"))
    )
    (net (code "100") (name "SWDCLK") (class "Default")
      (node (ref "J1") (pin "4") (pinfunction "4_4") (pintype "bidirectional"))
      (node (ref "P1.01/2.4B") (pin "P$AA24") (pinfunction "SWDCLK_P$AA24") (pintype "input"))
      (node (ref "TP_SDA3") (pin "TP") (pinfunction "TP_TP") (pintype "input"))
    )
    (net (code "101") (name "SWDIO") (class "Default")
      (node (ref "J1") (pin "2") (pinfunction "2_2") (pintype "bidirectional"))
      (node (ref "P1.01/2.4B") (pin "P$AC24") (pinfunction "SWDIO_P$AC24") (pintype "bidirectional"))
      (node (ref "TP_SDA2") (pin "TP") (pinfunction "TP_TP") (pintype "input"))
    )
    (net (code "102") (name "SWO") (class "Default")
      (node (ref "P1.01/2.4B") (pin "P$AD22") (pinfunction "P1.00_P$AD22") (pintype "bidirectional"))
      (node (ref "TP_SDA1") (pin "TP") (pinfunction "TP_TP") (pintype "input"))
    )
    (net (code "103") (name "VBAT{slash}1.2A") (class "Default")
      (node (ref "C2") (pin "2") (pinfunction "2_2") (pintype "passive"))
      (node (ref "TP_SDA9") (pin "TP") (pinfunction "TP_TP") (pintype "input"))
      (node (ref "U1") (pin "2") (pinfunction "CELL_2") (pintype "power_in"))
      (node (ref "U1") (pin "3") (pinfunction "VDD_3") (pintype "power_in"))
    )
    (net (code "104") (name "VBAT{slash}2.5C") (class "Default")
      (node (ref "C37") (pin "1") (pinfunction "1_1") (pintype "passive"))
      (node (ref "IC1") (pin "C2") (pinfunction "BAT_C2") (pintype "bidirectional"))
    )
    (net (code "105") (name "VBUS{slash}1.5D") (class "Default")
      (node (ref "C42") (pin "2") (pinfunction "2_2") (pintype "passive"))
      (node (ref "C43") (pin "1") (pinfunction "1_1") (pintype "passive"))
      (node (ref "D4") (pin "5") (pinfunction "VBUS_5") (pintype "bidirectional"))
      (node (ref "J3") (pin "A4_B9") (pinfunction "VBUS_A4_B9") (pintype "power_in"))
      (node (ref "J3") (pin "A9_B4") (pinfunction "VBUS_A9_B4") (pintype "power_in"))
    )
    (net (code "106") (name "VBUS{slash}2.6D") (class "Default")
      (node (ref "C21") (pin "1") (pinfunction "1_1") (pintype "passive"))
      (node (ref "C38") (pin "1") (pinfunction "1_1") (pintype "passive"))
      (node (ref "IC1") (pin "A2") (pinfunction "IN_A2") (pintype "bidirectional"))
      (node (ref "P1.01/2.4B") (pin "P$AD2") (pinfunction "VBUS_P$AD2") (pintype "power_in"))
    )
    (net (code "107") (name "VREG") (class "Default")
      (node (ref "C23") (pin "2") (pinfunction "2_2") (pintype "passive"))
      (node (ref "C24") (pin "2") (pinfunction "2_2") (pintype "passive"))
      (node (ref "C39") (pin "1") (pinfunction "1_1") (pintype "passive"))
      (node (ref "IC1") (pin "B2") (pinfunction "SYS_B2") (pintype "bidirectional"))
      (node (ref "IC2") (pin "A1") (pinfunction "EN_A1") (pintype "bidirectional"))
      (node (ref "IC2") (pin "A2") (pinfunction "VIN_1_A2") (pintype "bidirectional"))
      (node (ref "IC2") (pin "A3") (pinfunction "VIN_2_A3") (pintype "bidirectional"))
      (node (ref "TP_VREG") (pin "TP") (pinfunction "TP_TP") (pintype "input"))
    )
    (net (code "108") (name "unconnected-(ANT1-NC-Pad2)") (class "Default")
      (node (ref "ANT1") (pin "2") (pinfunction "NC_2") (pintype "no_connect"))
    )
    (net (code "109") (name "unconnected-(IC3-ASCL-Pad11)") (class "Default")
      (node (ref "IC3") (pin "11") (pinfunction "ASCL_11") (pintype "bidirectional"))
    )
    (net (code "110") (name "unconnected-(IC3-ASDA-Pad4)") (class "Default")
      (node (ref "IC3") (pin "4") (pinfunction "ASDA_4") (pintype "bidirectional"))
    )
    (net (code "111") (name "unconnected-(J2-Pad1)") (class "Default")
      (node (ref "J2") (pin "1") (pinfunction "1_1") (pintype "bidirectional"))
    )
    (net (code "112") (name "unconnected-(J2-Pad6)") (class "Default")
      (node (ref "J2") (pin "6") (pinfunction "6_6") (pintype "bidirectional"))
    )
    (net (code "113") (name "unconnected-(J2-Pad7)") (class "Default")
      (node (ref "J2") (pin "7") (pinfunction "7_7") (pintype "bidirectional"))
    )
    (net (code "114") (name "unconnected-(J3-SBU1-PadA8)") (class "Default")
      (node (ref "J3") (pin "A8") (pinfunction "SBU1_A8") (pintype "bidirectional"))
    )
    (net (code "115") (name "unconnected-(J3-SBU2-PadB8)") (class "Default")
      (node (ref "J3") (pin "B8") (pinfunction "SBU2_B8") (pintype "bidirectional"))
    )
    (net (code "116") (name "unconnected-(P1.01/2.4B-DCCH-PadP$AB2)") (class "Default")
      (node (ref "P1.01/2.4B") (pin "P$AB2") (pinfunction "DCCH_P$AB2") (pintype "bidirectional"))
    )
  )
)
